# oven-controller-v2.net
KiCad netlist of a schematic drawn in EAGLE
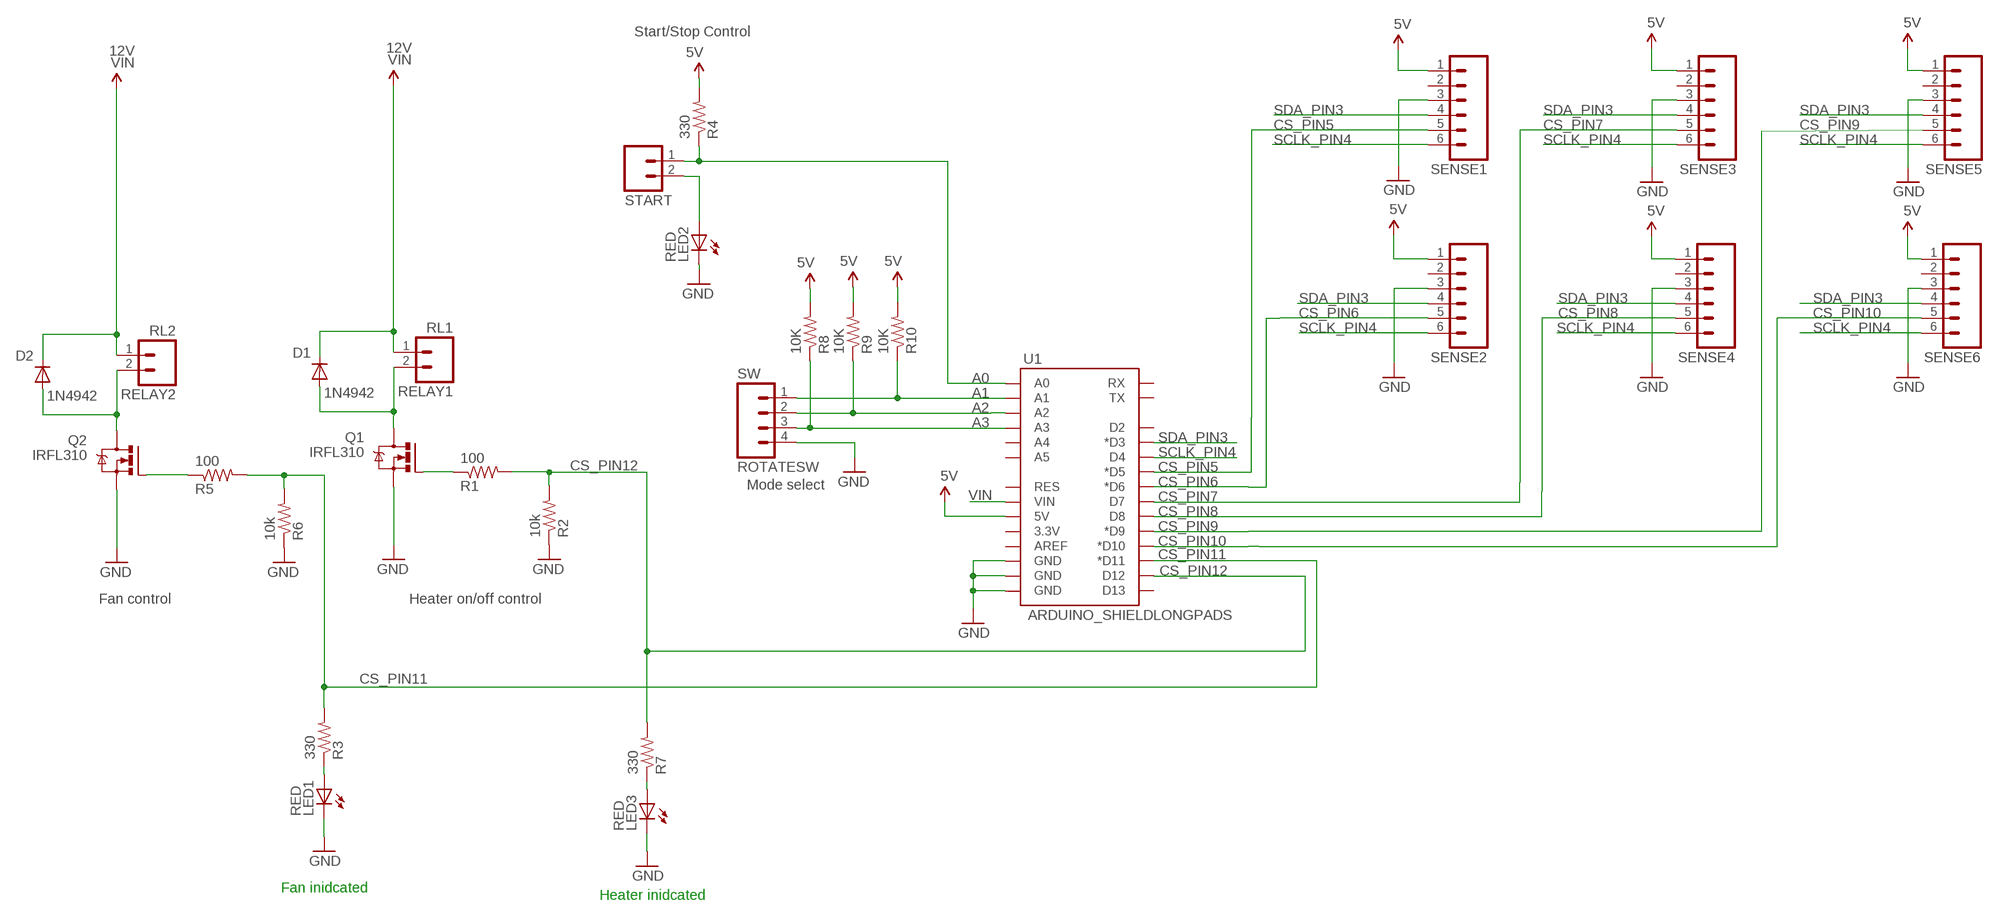
[diagram p0: schematic, sheet 1]

(export (version "E")
  (design (tool "Eeschema 10.0.6"))
  (components
    (comp (ref "D1")
      (value "1N4942")
      (footprint "eagle-import:DO41-10")
      (libsource (lib "eagle-import") (part "1N4942"))
    )
    (comp (ref "D2")
      (value "1N4942")
      (footprint "eagle-import:DO41-10")
      (libsource (lib "eagle-import") (part "1N4942"))
    )
    (comp (ref "LED1")
      (value "RED")
      (footprint "eagle-import:LED5MM")
      (libsource (lib "eagle-import") (part "LED5MM"))
    )
    (comp (ref "LED2")
      (value "RED")
      (footprint "eagle-import:LED5MM")
      (libsource (lib "eagle-import") (part "LED5MM"))
    )
    (comp (ref "LED3")
      (value "RED")
      (footprint "eagle-import:LED5MM")
      (libsource (lib "eagle-import") (part "LED5MM"))
    )
    (comp (ref "Q1")
      (value "IRFL310")
      (footprint "eagle-import:TO220BV")
      (libsource (lib "eagle-import") (part "IRF520"))
    )
    (comp (ref "Q2")
      (value "IRFL310")
      (footprint "eagle-import:TO220BV")
      (libsource (lib "eagle-import") (part "IRF520"))
    )
    (comp (ref "R1")
      (value "100")
      (footprint "eagle-import:AXIAL-0.3")
      (libsource (lib "eagle-import") (part "RESISTORAXIAL-0.3"))
    )
    (comp (ref "R2")
      (value "10k")
      (footprint "eagle-import:AXIAL-0.3")
      (libsource (lib "eagle-import") (part "RESISTORAXIAL-0.3"))
    )
    (comp (ref "R3")
      (value "330")
      (footprint "eagle-import:AXIAL-0.3")
      (libsource (lib "eagle-import") (part "RESISTORAXIAL-0.3"))
    )
    (comp (ref "R4")
      (value "330")
      (footprint "eagle-import:AXIAL-0.3")
      (libsource (lib "eagle-import") (part "RESISTORAXIAL-0.3"))
    )
    (comp (ref "R5")
      (value "100")
      (footprint "eagle-import:AXIAL-0.3")
      (libsource (lib "eagle-import") (part "RESISTORAXIAL-0.3"))
    )
    (comp (ref "R6")
      (value "10k")
      (footprint "eagle-import:AXIAL-0.3")
      (libsource (lib "eagle-import") (part "RESISTORAXIAL-0.3"))
    )
    (comp (ref "R7")
      (value "330")
      (footprint "eagle-import:AXIAL-0.3")
      (libsource (lib "eagle-import") (part "RESISTORAXIAL-0.3"))
    )
    (comp (ref "R8")
      (value "10K")
      (footprint "eagle-import:AXIAL-0.3")
      (libsource (lib "eagle-import") (part "RESISTORAXIAL-0.3"))
    )
    (comp (ref "R9")
      (value "10K")
      (footprint "eagle-import:AXIAL-0.3")
      (libsource (lib "eagle-import") (part "RESISTORAXIAL-0.3"))
    )
    (comp (ref "R10")
      (value "10K")
      (footprint "eagle-import:AXIAL-0.3")
      (libsource (lib "eagle-import") (part "RESISTORAXIAL-0.3"))
    )
    (comp (ref "RELAY1")
      (value "RL1")
      (footprint "eagle-import:SCREWTERMINAL-3.5MM-2_LOCK")
      (libsource (lib "eagle-import") (part "M023.5MM_LOCK"))
    )
    (comp (ref "RELAY2")
      (value "RL2")
      (footprint "eagle-import:SCREWTERMINAL-3.5MM-2_LOCK")
      (libsource (lib "eagle-import") (part "M023.5MM_LOCK"))
    )
    (comp (ref "ROTATESW")
      (value "SW")
      (footprint "eagle-import:1X04_LOCK_LONGPADS")
      (libsource (lib "eagle-import") (part "M04LOCK_LONGPADS"))
    )
    (comp (ref "SENSE1")
      (value "M06LOCK_LONGPADS")
      (footprint "eagle-import:1X06_LOCK_LONGPADS")
      (libsource (lib "eagle-import") (part "M06LOCK_LONGPADS"))
    )
    (comp (ref "SENSE2")
      (value "M06LOCK_LONGPADS")
      (footprint "eagle-import:1X06_LOCK_LONGPADS")
      (libsource (lib "eagle-import") (part "M06LOCK_LONGPADS"))
    )
    (comp (ref "SENSE3")
      (value "M06LOCK_LONGPADS")
      (footprint "eagle-import:1X06_LOCK_LONGPADS")
      (libsource (lib "eagle-import") (part "M06LOCK_LONGPADS"))
    )
    (comp (ref "SENSE4")
      (value "M06LOCK_LONGPADS")
      (footprint "eagle-import:1X06_LOCK_LONGPADS")
      (libsource (lib "eagle-import") (part "M06LOCK_LONGPADS"))
    )
    (comp (ref "SENSE5")
      (value "M06LOCK_LONGPADS")
      (footprint "eagle-import:1X06_LOCK_LONGPADS")
      (libsource (lib "eagle-import") (part "M06LOCK_LONGPADS"))
    )
    (comp (ref "SENSE6")
      (value "M06LOCK_LONGPADS")
      (footprint "eagle-import:1X06_LOCK_LONGPADS")
      (libsource (lib "eagle-import") (part "M06LOCK_LONGPADS"))
    )
    (comp (ref "START")
      (value "M023.5MM_LOCK")
      (footprint "eagle-import:SCREWTERMINAL-3.5MM-2_LOCK")
      (libsource (lib "eagle-import") (part "M023.5MM_LOCK"))
    )
    (comp (ref "U1")
      (value "ARDUINO_SHIELDLONGPADS")
      (footprint "eagle-import:DUEMILANOVE_SHIELD_LONGPADS")
      (libsource (lib "eagle-import") (part "ARDUINO_SHIELDLONGPADS"))
    )
  )
  (nets
    (net (code "1") (name "/A0") (class "Default")
      (node (ref "R4") (pin "P$1") (pinfunction "1_P$1") (pintype "passive"))
      (node (ref "START") (pin "1") (pinfunction "1_1") (pintype "passive"))
      (node (ref "U1") (pin "A0") (pinfunction "A0_A0") (pintype "bidirectional"))
    )
    (net (code "2") (name "/A1") (class "Default")
      (node (ref "R10") (pin "P$1") (pinfunction "1_P$1") (pintype "passive"))
      (node (ref "ROTATESW") (pin "1") (pinfunction "1_1") (pintype "passive"))
      (node (ref "U1") (pin "A1") (pinfunction "A1_A1") (pintype "bidirectional"))
    )
    (net (code "3") (name "/A2") (class "Default")
      (node (ref "R9") (pin "P$1") (pinfunction "1_P$1") (pintype "passive"))
      (node (ref "ROTATESW") (pin "2") (pinfunction "2_2") (pintype "passive"))
      (node (ref "U1") (pin "A2") (pinfunction "A2_A2") (pintype "bidirectional"))
    )
    (net (code "4") (name "/A3") (class "Default")
      (node (ref "R8") (pin "P$1") (pinfunction "1_P$1") (pintype "passive"))
      (node (ref "ROTATESW") (pin "3") (pinfunction "3_3") (pintype "passive"))
      (node (ref "U1") (pin "A3") (pinfunction "A3_A3") (pintype "bidirectional"))
    )
    (net (code "5") (name "/CS_PIN5") (class "Default")
      (node (ref "SENSE1") (pin "5") (pinfunction "5_5") (pintype "passive"))
      (node (ref "U1") (pin "D5") (pinfunction "*D5_D5") (pintype "bidirectional"))
    )
    (net (code "6") (name "/CS_PIN6") (class "Default")
      (node (ref "SENSE2") (pin "5") (pinfunction "5_5") (pintype "passive"))
      (node (ref "U1") (pin "D6") (pinfunction "*D6_D6") (pintype "bidirectional"))
    )
    (net (code "7") (name "/CS_PIN7") (class "Default")
      (node (ref "SENSE3") (pin "5") (pinfunction "5_5") (pintype "passive"))
      (node (ref "U1") (pin "D7") (pinfunction "D7_D7") (pintype "bidirectional"))
    )
    (net (code "8") (name "/CS_PIN8") (class "Default")
      (node (ref "SENSE4") (pin "5") (pinfunction "5_5") (pintype "passive"))
      (node (ref "U1") (pin "D8") (pinfunction "D8_D8") (pintype "bidirectional"))
    )
    (net (code "9") (name "/CS_PIN9") (class "Default")
      (node (ref "SENSE5") (pin "5") (pinfunction "5_5") (pintype "passive"))
      (node (ref "U1") (pin "D9") (pinfunction "*D9_D9") (pintype "bidirectional"))
    )
    (net (code "10") (name "/CS_PIN10") (class "Default")
      (node (ref "SENSE6") (pin "5") (pinfunction "5_5") (pintype "passive"))
      (node (ref "U1") (pin "D10") (pinfunction "*D10_D10") (pintype "bidirectional"))
    )
    (net (code "11") (name "/CS_PIN11") (class "Default")
      (node (ref "R3") (pin "P$2") (pinfunction "2_P$2") (pintype "passive"))
      (node (ref "R5") (pin "P$2") (pinfunction "2_P$2") (pintype "passive"))
      (node (ref "R6") (pin "P$2") (pinfunction "2_P$2") (pintype "passive"))
      (node (ref "U1") (pin "D11") (pinfunction "*D11_D11") (pintype "bidirectional"))
    )
    (net (code "12") (name "/CS_PIN12") (class "Default")
      (node (ref "R1") (pin "P$2") (pinfunction "2_P$2") (pintype "passive"))
      (node (ref "R2") (pin "P$2") (pinfunction "2_P$2") (pintype "passive"))
      (node (ref "R7") (pin "P$2") (pinfunction "2_P$2") (pintype "passive"))
      (node (ref "U1") (pin "D12") (pinfunction "D12_D12") (pintype "bidirectional"))
    )
    (net (code "13") (name "/SCLK_PIN4") (class "Default")
      (node (ref "SENSE1") (pin "6") (pinfunction "6_6") (pintype "passive"))
      (node (ref "SENSE2") (pin "6") (pinfunction "6_6") (pintype "passive"))
      (node (ref "SENSE3") (pin "6") (pinfunction "6_6") (pintype "passive"))
      (node (ref "SENSE4") (pin "6") (pinfunction "6_6") (pintype "passive"))
      (node (ref "SENSE5") (pin "6") (pinfunction "6_6") (pintype "passive"))
      (node (ref "SENSE6") (pin "6") (pinfunction "6_6") (pintype "passive"))
      (node (ref "U1") (pin "D4") (pinfunction "D4_D4") (pintype "bidirectional"))
    )
    (net (code "14") (name "/SDA_PIN3") (class "Default")
      (node (ref "SENSE1") (pin "4") (pinfunction "4_4") (pintype "passive"))
      (node (ref "SENSE2") (pin "4") (pinfunction "4_4") (pintype "passive"))
      (node (ref "SENSE3") (pin "4") (pinfunction "4_4") (pintype "passive"))
      (node (ref "SENSE4") (pin "4") (pinfunction "4_4") (pintype "passive"))
      (node (ref "SENSE5") (pin "4") (pinfunction "4_4") (pintype "passive"))
      (node (ref "SENSE6") (pin "4") (pinfunction "4_4") (pintype "passive"))
      (node (ref "U1") (pin "D3") (pinfunction "*D3_D3") (pintype "bidirectional"))
    )
    (net (code "15") (name "5V") (class "Default")
      (node (ref "R10") (pin "P$2") (pinfunction "2_P$2") (pintype "passive"))
      (node (ref "R4") (pin "P$2") (pinfunction "2_P$2") (pintype "passive"))
      (node (ref "R8") (pin "P$2") (pinfunction "2_P$2") (pintype "passive"))
      (node (ref "R9") (pin "P$2") (pinfunction "2_P$2") (pintype "passive"))
      (node (ref "SENSE1") (pin "1") (pinfunction "1_1") (pintype "passive"))
      (node (ref "SENSE2") (pin "1") (pinfunction "1_1") (pintype "passive"))
      (node (ref "SENSE3") (pin "1") (pinfunction "1_1") (pintype "passive"))
      (node (ref "SENSE4") (pin "1") (pinfunction "1_1") (pintype "passive"))
      (node (ref "SENSE5") (pin "1") (pinfunction "1_1") (pintype "passive"))
      (node (ref "SENSE6") (pin "1") (pinfunction "1_1") (pintype "passive"))
      (node (ref "U1") (pin "5V") (pinfunction "5V_5V") (pintype "bidirectional"))
    )
    (net (code "16") (name "GND") (class "Default")
      (node (ref "LED1") (pin "K") (pinfunction "C_K") (pintype "passive"))
      (node (ref "LED2") (pin "K") (pinfunction "C_K") (pintype "passive"))
      (node (ref "LED3") (pin "K") (pinfunction "C_K") (pintype "passive"))
      (node (ref "Q1") (pin "S") (pinfunction "S_S") (pintype "passive"))
      (node (ref "Q2") (pin "S") (pinfunction "S_S") (pintype "passive"))
      (node (ref "R2") (pin "P$1") (pinfunction "1_P$1") (pintype "passive"))
      (node (ref "R6") (pin "P$1") (pinfunction "1_P$1") (pintype "passive"))
      (node (ref "ROTATESW") (pin "4") (pinfunction "4_4") (pintype "passive"))
      (node (ref "SENSE1") (pin "3") (pinfunction "3_3") (pintype "passive"))
      (node (ref "SENSE2") (pin "3") (pinfunction "3_3") (pintype "passive"))
      (node (ref "SENSE3") (pin "3") (pinfunction "3_3") (pintype "passive"))
      (node (ref "SENSE4") (pin "3") (pinfunction "3_3") (pintype "passive"))
      (node (ref "SENSE5") (pin "3") (pinfunction "3_3") (pintype "passive"))
      (node (ref "SENSE6") (pin "3") (pinfunction "3_3") (pintype "passive"))
      (node (ref "U1") (pin "GND@0") (pinfunction "GND_GND@0") (pintype "bidirectional"))
      (node (ref "U1") (pin "GND@1") (pinfunction "GND_GND@1") (pintype "bidirectional"))
      (node (ref "U1") (pin "GND@2") (pinfunction "GND_GND@2") (pintype "bidirectional"))
    )
    (net (code "17") (name "Net-(D1-PadA)") (class "Default")
      (node (ref "D1") (pin "A") (pinfunction "A_A") (pintype "passive"))
      (node (ref "Q1") (pin "D") (pinfunction "D_D") (pintype "passive"))
      (node (ref "RELAY1") (pin "2") (pinfunction "2_2") (pintype "passive"))
    )
    (net (code "18") (name "Net-(D2-PadA)") (class "Default")
      (node (ref "D2") (pin "A") (pinfunction "A_A") (pintype "passive"))
      (node (ref "Q2") (pin "D") (pinfunction "D_D") (pintype "passive"))
      (node (ref "RELAY2") (pin "2") (pinfunction "2_2") (pintype "passive"))
    )
    (net (code "19") (name "Net-(LED2-PadA)") (class "Default")
      (node (ref "LED2") (pin "A") (pinfunction "A_A") (pintype "passive"))
      (node (ref "START") (pin "2") (pinfunction "2_2") (pintype "passive"))
    )
    (net (code "20") (name "Net-(R1-1)") (class "Default")
      (node (ref "Q1") (pin "G") (pinfunction "G_G") (pintype "passive"))
      (node (ref "R1") (pin "P$1") (pinfunction "1_P$1") (pintype "passive"))
    )
    (net (code "21") (name "Net-(R3-1)") (class "Default")
      (node (ref "LED1") (pin "A") (pinfunction "A_A") (pintype "passive"))
      (node (ref "R3") (pin "P$1") (pinfunction "1_P$1") (pintype "passive"))
    )
    (net (code "22") (name "Net-(R5-1)") (class "Default")
      (node (ref "Q2") (pin "G") (pinfunction "G_G") (pintype "passive"))
      (node (ref "R5") (pin "P$1") (pinfunction "1_P$1") (pintype "passive"))
    )
    (net (code "23") (name "Net-(R7-1)") (class "Default")
      (node (ref "LED3") (pin "A") (pinfunction "A_A") (pintype "passive"))
      (node (ref "R7") (pin "P$1") (pinfunction "1_P$1") (pintype "passive"))
    )
    (net (code "24") (name "VIN") (class "Default")
      (node (ref "D1") (pin "C") (pinfunction "C_C") (pintype "passive"))
      (node (ref "D2") (pin "C") (pinfunction "C_C") (pintype "passive"))
      (node (ref "RELAY1") (pin "1") (pinfunction "1_1") (pintype "passive"))
      (node (ref "RELAY2") (pin "1") (pinfunction "1_1") (pintype "passive"))
      (node (ref "U1") (pin "VIN") (pinfunction "VIN_VIN") (pintype "bidirectional"))
    )
    (net (code "25") (name "unconnected-(SENSE1-Pad2)") (class "Default")
      (node (ref "SENSE1") (pin "2") (pinfunction "2_2") (pintype "passive"))
    )
    (net (code "26") (name "unconnected-(SENSE2-Pad2)") (class "Default")
      (node (ref "SENSE2") (pin "2") (pinfunction "2_2") (pintype "passive"))
    )
    (net (code "27") (name "unconnected-(SENSE3-Pad2)") (class "Default")
      (node (ref "SENSE3") (pin "2") (pinfunction "2_2") (pintype "passive"))
    )
    (net (code "28") (name "unconnected-(SENSE4-Pad2)") (class "Default")
      (node (ref "SENSE4") (pin "2") (pinfunction "2_2") (pintype "passive"))
    )
    (net (code "29") (name "unconnected-(SENSE5-Pad2)") (class "Default")
      (node (ref "SENSE5") (pin "2") (pinfunction "2_2") (pintype "passive"))
    )
    (net (code "30") (name "unconnected-(SENSE6-Pad2)") (class "Default")
      (node (ref "SENSE6") (pin "2") (pinfunction "2_2") (pintype "passive"))
    )
    (net (code "31") (name "unconnected-(U1-Pad3.3V)") (class "Default")
      (node (ref "U1") (pin "3.3V") (pinfunction "3.3V_3.3V") (pintype "bidirectional"))
    )
    (net (code "32") (name "unconnected-(U1-PadA4)") (class "Default")
      (node (ref "U1") (pin "A4") (pinfunction "A4_A4") (pintype "bidirectional"))
    )
    (net (code "33") (name "unconnected-(U1-PadA5)") (class "Default")
      (node (ref "U1") (pin "A5") (pinfunction "A5_A5") (pintype "bidirectional"))
    )
    (net (code "34") (name "unconnected-(U1-PadAREF)") (class "Default")
      (node (ref "U1") (pin "AREF") (pinfunction "AREF_AREF") (pintype "bidirectional"))
    )
    (net (code "35") (name "unconnected-(U1-PadD2)") (class "Default")
      (node (ref "U1") (pin "D2") (pinfunction "D2_D2") (pintype "bidirectional"))
    )
    (net (code "36") (name "unconnected-(U1-PadD13)") (class "Default")
      (node (ref "U1") (pin "D13") (pinfunction "D13_D13") (pintype "bidirectional"))
    )
    (net (code "37") (name "unconnected-(U1-PadRES)") (class "Default")
      (node (ref "U1") (pin "RES") (pinfunction "RES_RES") (pintype "bidirectional"))
    )
    (net (code "38") (name "unconnected-(U1-PadRX)") (class "Default")
      (node (ref "U1") (pin "RX") (pinfunction "RX_RX") (pintype "bidirectional"))
    )
    (net (code "39") (name "unconnected-(U1-PadTX)") (class "Default")
      (node (ref "U1") (pin "TX") (pinfunction "TX_TX") (pintype "bidirectional"))
    )
  )
)
